# Sheet1.net
KiCad netlist of a schematic drawn in Altium Designer
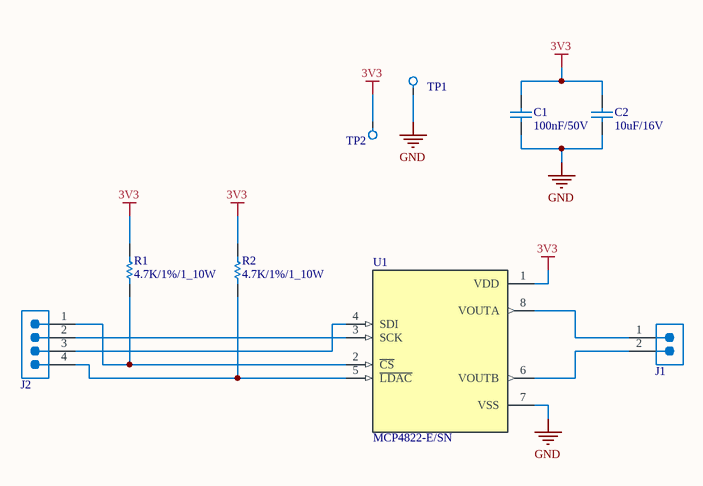
[diagram p0: Sheet1.SchDoc]

(export (version "E")
  (design (tool "Eeschema 10.0.6"))
  (components
    (comp (ref "C1")
      (value "100nF/50V")
      (footprint "CAP_0603")
      (description "CAP, size 0603, 100nF, 50V")
      (fields (field (name "SUPPLY PART NUMBER") "Tụ Gốm 0603 100nF (0.1uF) 50V"))
      (libsource (lib "BluetoothTracking") (part "Ceramic_Cap_100nF_50V_0603"))
    )
    (comp (ref "C2")
      (value "10uF/16V")
      (footprint "CAP_0603")
      (description "CAP, size 0603, 10uF, 16V")
      (fields (field (name "SUPPLY PART NUMBER") "Tụ Gốm 0603 10uF 16V"))
      (libsource (lib "BluetoothTracking") (part "Ceramic_Cap_10uF_16V_0603"))
    )
    (comp (ref "J1")
      (value "2.54mm_2P")
      (footprint "Header_2.54mm_2P")
      (description "Hàng Rào Đực Đơn 2.54mm 40 Chân 1 Hàng Cao 11.2mm Xuyên Lỗ")
      (libsource (lib "BluetoothTracking") (part "Header_2.54mm_2P"))
    )
    (comp (ref "J2")
      (value "2.54mm_4P")
      (footprint "Header_2.54mm_4P")
      (description "Hàng Rào Đực Đơn 2.54mm 40 Chân 1 Hàng Cao 11.2mm Xuyên Lỗ")
      (libsource (lib "BluetoothTracking") (part "Header_2.54mm_4P"))
    )
    (comp (ref "R1")
      (value "4.7K/1%/1_10W")
      (footprint "Resistor_0603")
      (description "Resistor 0603 4.7KOhm 1% 1_10W")
      (fields (field (name "SUPPLY PART NUMBER") "Điện Trở 4.7 KOhm 0603 1%"))
      (libsource (lib "BluetoothTracking") (part "Res_4.7K_0603_1%"))
    )
    (comp (ref "R2")
      (value "4.7K/1%/1_10W")
      (footprint "Resistor_0603")
      (description "Resistor 0603 4.7KOhm 1% 1_10W")
      (fields (field (name "SUPPLY PART NUMBER") "Điện Trở 4.7 KOhm 0603 1%"))
      (libsource (lib "BluetoothTracking") (part "Res_4.7K_0603_1%"))
    )
    (comp (ref "TP1")
      (value "Testpoint_SMD")
      (footprint "TestPoint_Pad_2.0x2.0mm")
      (libsource (lib "BluetoothTracking") (part "Testpoint_SMD"))
    )
    (comp (ref "TP2")
      (value "Testpoint_SMD")
      (footprint "TestPoint_Pad_2.0x2.0mm")
      (libsource (lib "BluetoothTracking") (part "Testpoint_SMD"))
    )
    (comp (ref "U1")
      (value "MCP4822-E/SN")
      (footprint "SOIC-8")
      (description "12 Bit Digital to Analog Converter 2 8-SOIC")
      (fields (field (name "SUPPLY PART NUMBER") "MCP4822-E/SN SOIC-8 DAC 12Bit Chính Hãng Microchip"))
      (libsource (lib "BluetoothTracking") (part "MCP4822-E/SN"))
    )
  )
  (nets
    (net (code "1") (name "3V3") (class "Default")
      (node (ref "C1") (pin "2") (pinfunction "2_2") (pintype "passive"))
      (node (ref "C2") (pin "2") (pinfunction "2_2") (pintype "passive"))
      (node (ref "R1") (pin "2") (pinfunction "2_2") (pintype "passive"))
      (node (ref "R2") (pin "2") (pinfunction "2_2") (pintype "passive"))
      (node (ref "TP2") (pin "1") (pinfunction "1_1") (pintype "passive"))
      (node (ref "U1") (pin "1") (pinfunction "VDD_1") (pintype "power_in"))
    )
    (net (code "2") (name "GND") (class "Default")
      (node (ref "C1") (pin "1") (pinfunction "1_1") (pintype "passive"))
      (node (ref "C2") (pin "1") (pinfunction "1_1") (pintype "passive"))
      (node (ref "TP1") (pin "1") (pinfunction "1_1") (pintype "passive"))
      (node (ref "U1") (pin "7") (pinfunction "VSS_7") (pintype "power_in"))
    )
    (net (code "3") (name "Net-(U1-SCK)") (class "Default")
      (node (ref "J2") (pin "2") (pinfunction "2_2") (pintype "passive"))
      (node (ref "U1") (pin "3") (pinfunction "SCK_3") (pintype "input"))
    )
    (net (code "4") (name "Net-(U1-SDI)") (class "Default")
      (node (ref "J2") (pin "3") (pinfunction "3_3") (pintype "passive"))
      (node (ref "U1") (pin "4") (pinfunction "SDI_4") (pintype "input"))
    )
    (net (code "5") (name "Net-(U1-VOUTA)") (class "Default")
      (node (ref "J1") (pin "1") (pinfunction "1_1") (pintype "passive"))
      (node (ref "U1") (pin "8") (pinfunction "VOUTA_8") (pintype "output"))
    )
    (net (code "6") (name "Net-(U1-VOUTB)") (class "Default")
      (node (ref "J1") (pin "2") (pinfunction "2_2") (pintype "passive"))
      (node (ref "U1") (pin "6") (pinfunction "VOUTB_6") (pintype "output"))
    )
    (net (code "7") (name "Net-(U1-~{CS})") (class "Default")
      (node (ref "J2") (pin "1") (pinfunction "1_1") (pintype "passive"))
      (node (ref "R1") (pin "1") (pinfunction "1_1") (pintype "passive"))
      (node (ref "U1") (pin "2") (pinfunction "~{CS}_2") (pintype "input"))
    )
    (net (code "8") (name "Net-(U1-~{LDAC})") (class "Default")
      (node (ref "J2") (pin "4") (pinfunction "4_4") (pintype "passive"))
      (node (ref "R2") (pin "1") (pinfunction "1_1") (pintype "passive"))
      (node (ref "U1") (pin "5") (pinfunction "~{LDAC}_5") (pintype "input"))
    )
  )
)
